# Power.net
KiCad netlist of a schematic drawn in Altium Designer
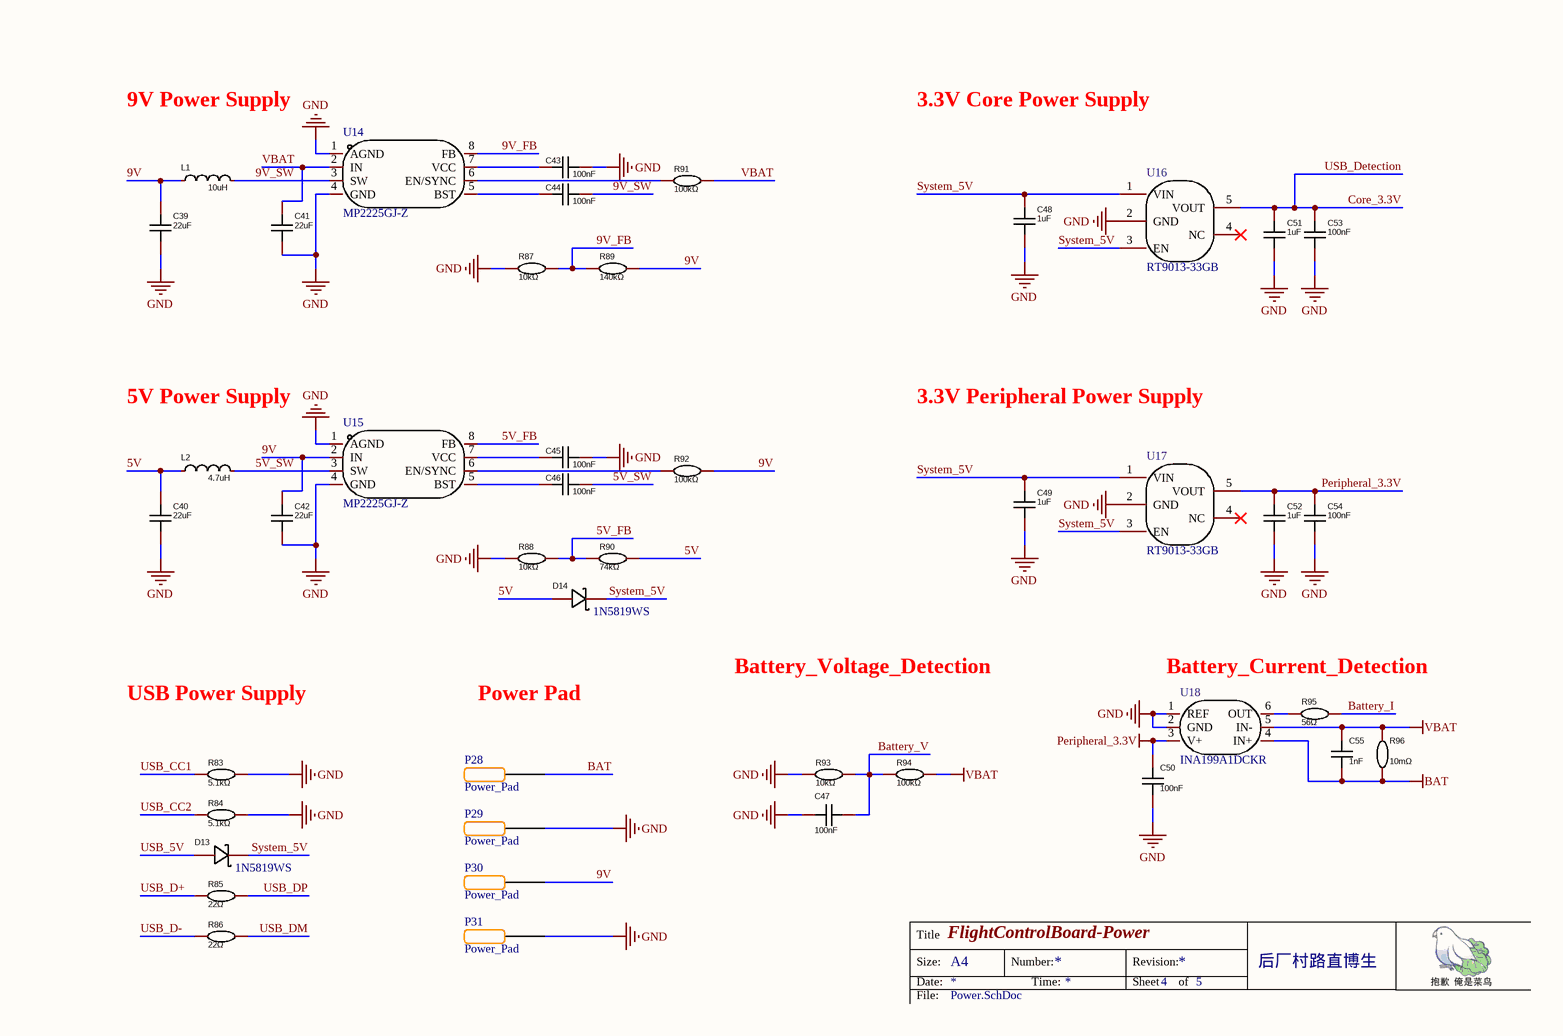
[diagram p0: Power.SchDoc]

(export (version "E")
  (design (tool "Eeschema 10.0.6"))
  (components
    (comp (ref "C39")
      (value "22uF")
      (footprint "C0603")
      (libsource (lib "Capacitor") (part "CC0603KRX7R9BB104"))
    )
    (comp (ref "C40")
      (value "22uF")
      (footprint "C0603")
      (libsource (lib "Capacitor") (part "CC0603KRX7R9BB104"))
    )
    (comp (ref "C41")
      (value "22uF")
      (footprint "C0603")
      (libsource (lib "Capacitor") (part "CC0603KRX7R9BB104"))
    )
    (comp (ref "C42")
      (value "22uF")
      (footprint "C0603")
      (libsource (lib "Capacitor") (part "CC0603KRX7R9BB104"))
    )
    (comp (ref "C43")
      (value "100nF")
      (footprint "C0201")
      (libsource (lib "Capacitor") (part "CC0603KRX7R9BB104"))
    )
    (comp (ref "C44")
      (value "100nF")
      (footprint "C0201")
      (libsource (lib "Capacitor") (part "CC0603KRX7R9BB104"))
    )
    (comp (ref "C45")
      (value "100nF")
      (footprint "C0201")
      (libsource (lib "Capacitor") (part "CC0603KRX7R9BB104"))
    )
    (comp (ref "C46")
      (value "100nF")
      (footprint "C0201")
      (libsource (lib "Capacitor") (part "CC0603KRX7R9BB104"))
    )
    (comp (ref "C47")
      (value "100nF")
      (footprint "C0201")
      (libsource (lib "Capacitor") (part "CC0603KRX7R9BB104"))
    )
    (comp (ref "C48")
      (value "1uF")
      (footprint "C0402")
      (libsource (lib "Capacitor") (part "CC0603KRX7R9BB104"))
    )
    (comp (ref "C49")
      (value "1uF")
      (footprint "C0402")
      (libsource (lib "Capacitor") (part "CC0603KRX7R9BB104"))
    )
    (comp (ref "C50")
      (value "100nF")
      (footprint "C0201")
      (libsource (lib "Capacitor") (part "CC0603KRX7R9BB104"))
    )
    (comp (ref "C51")
      (value "1uF")
      (footprint "C0402")
      (libsource (lib "Capacitor") (part "CC0603KRX7R9BB104"))
    )
    (comp (ref "C52")
      (value "1uF")
      (footprint "C0402")
      (libsource (lib "Capacitor") (part "CC0603KRX7R9BB104"))
    )
    (comp (ref "C53")
      (value "100nF")
      (footprint "C0201")
      (libsource (lib "Capacitor") (part "CC0603KRX7R9BB104"))
    )
    (comp (ref "C54")
      (value "100nF")
      (footprint "C0201")
      (libsource (lib "Capacitor") (part "CC0603KRX7R9BB104"))
    )
    (comp (ref "C55")
      (value "1nF")
      (footprint "C0201")
      (libsource (lib "Capacitor") (part "CC0603KRX7R9BB104"))
    )
    (comp (ref "D13")
      (value "1N5819WS")
      (footprint "SOD-323")
      (fields (field (name "MANUFACTURER") "Hottech(合科泰)"))
      (libsource (lib "Diode") (part "1N5819WS"))
    )
    (comp (ref "D14")
      (value "1N5819WS")
      (footprint "SOD-323")
      (fields (field (name "MANUFACTURER") "Hottech(合科泰)"))
      (libsource (lib "Diode") (part "1N5819WS"))
    )
    (comp (ref "L1")
      (value "10uH")
      (footprint "IND-SMD_L4.0-W4.0")
      (fields
        (field (name "MANUFACTURER") "cjiang(长江微电)")
        (field (name "MANUFACTURER PART") "FHD4020S-100MT")
        (field (name "TOLERANCE") "±10%")
      )
      (libsource (lib "Inductor") (part "SDFL2012T220KTF"))
    )
    (comp (ref "L2")
      (value "4.7uH")
      (footprint "IND-SMD_L4.0-W4.0")
      (fields
        (field (name "MANUFACTURER") "cjiang(长江微电)")
        (field (name "MANUFACTURER PART") "FHD4020S-4R7MT")
        (field (name "TOLERANCE") "±10%")
      )
      (libsource (lib "Inductor") (part "SDFL2012T220KTF"))
    )
    (comp (ref "P28")
      (value "Power_Pad")
      (footprint "POWER HALF HOLE")
      (libsource (lib "Pad") (part "Power_Pad"))
    )
    (comp (ref "P29")
      (value "Power_Pad")
      (footprint "POWER HALF HOLE")
      (libsource (lib "Pad") (part "Power_Pad"))
    )
    (comp (ref "P30")
      (value "Power_Pad")
      (footprint "POWER HALF HOLE")
      (libsource (lib "Pad") (part "Power_Pad"))
    )
    (comp (ref "P31")
      (value "Power_Pad")
      (footprint "POWER HALF HOLE")
      (libsource (lib "Pad") (part "Power_Pad"))
    )
    (comp (ref "R83")
      (value "5.1kΩ")
      (footprint "R0201")
      (libsource (lib "Resistor") (part "0603WAF1002T5E"))
    )
    (comp (ref "R84")
      (value "5.1kΩ")
      (footprint "R0201")
      (libsource (lib "Resistor") (part "0603WAF1002T5E"))
    )
    (comp (ref "R85") (value "22Ω") (footprint "R0201") (libsource (lib "Resistor") (part "0603WAF1002T5E")))
    (comp (ref "R86") (value "22Ω") (footprint "R0201") (libsource (lib "Resistor") (part "0603WAF1002T5E")))
    (comp (ref "R87") (value "10kΩ") (footprint "R0201") (libsource (lib "Resistor") (part "0603WAF1002T5E")))
    (comp (ref "R88") (value "10kΩ") (footprint "R0201") (libsource (lib "Resistor") (part "0603WAF1002T5E")))
    (comp (ref "R89")
      (value "140kΩ")
      (footprint "R0201")
      (libsource (lib "Resistor") (part "0603WAF1002T5E"))
    )
    (comp (ref "R90") (value "74kΩ") (footprint "R0201") (libsource (lib "Resistor") (part "0603WAF1002T5E")))
    (comp (ref "R91")
      (value "100kΩ")
      (footprint "R0201")
      (libsource (lib "Resistor") (part "0603WAF1002T5E"))
    )
    (comp (ref "R92")
      (value "100kΩ")
      (footprint "R0201")
      (libsource (lib "Resistor") (part "0603WAF1002T5E"))
    )
    (comp (ref "R93") (value "10kΩ") (footprint "R0201") (libsource (lib "Resistor") (part "0603WAF1002T5E")))
    (comp (ref "R94")
      (value "100kΩ")
      (footprint "R0201")
      (libsource (lib "Resistor") (part "0603WAF1002T5E"))
    )
    (comp (ref "R95") (value "56Ω") (footprint "R0201") (libsource (lib "Resistor") (part "0603WAF1002T5E")))
    (comp (ref "R96") (value "10mΩ") (footprint "R0805") (libsource (lib "Resistor") (part "0603WAF1002T5E")))
    (comp (ref "U14")
      (value "MP2225GJ-Z")
      (footprint "SOT-23-8")
      (libsource (lib "Power") (part "MP2225GJ-Z"))
    )
    (comp (ref "U15")
      (value "MP2225GJ-Z")
      (footprint "SOT-23-8")
      (libsource (lib "Power") (part "MP2225GJ-Z"))
    )
    (comp (ref "U16")
      (value "RT9013-33GB")
      (footprint "SOT-23-5")
      (fields (field (name "MANUFACTURER") "RICHTEK(立锜)"))
      (libsource (lib "Power") (part "RT9013-33GB"))
    )
    (comp (ref "U17")
      (value "RT9013-33GB")
      (footprint "SOT-23-5")
      (fields (field (name "MANUFACTURER") "RICHTEK(立锜)"))
      (libsource (lib "Power") (part "RT9013-33GB"))
    )
    (comp (ref "U18")
      (value "INA199A1DCKR")
      (footprint "SOT-323-6")
      (fields (field (name "MANUFACTURER") "TI(德州仪器)"))
      (libsource (lib "ESC_Drive") (part "INA199A1DCKR"))
    )
  )
  (nets
    (net (code "1") (name "/5V") (class "Default")
      (node (ref "C40") (pin "1") (pinfunction "1_1") (pintype "passive"))
      (node (ref "D14") (pin "2") (pinfunction "A_2") (pintype "passive"))
      (node (ref "L2") (pin "1") (pinfunction "1_1") (pintype "passive"))
      (node (ref "R90") (pin "2") (pinfunction "2_2") (pintype "passive"))
    )
    (net (code "2") (name "/5V_FB") (class "Default")
      (node (ref "R88") (pin "2") (pinfunction "2_2") (pintype "passive"))
      (node (ref "R90") (pin "1") (pinfunction "1_1") (pintype "passive"))
      (node (ref "U15") (pin "8") (pinfunction "FB_8") (pintype "passive"))
    )
    (net (code "3") (name "/5V_SW") (class "Default")
      (node (ref "C46") (pin "1") (pinfunction "1_1") (pintype "passive"))
      (node (ref "L2") (pin "2") (pinfunction "2_2") (pintype "passive"))
      (node (ref "U15") (pin "3") (pinfunction "SW_3") (pintype "passive"))
    )
    (net (code "4") (name "/9V") (class "Default")
      (node (ref "C39") (pin "1") (pinfunction "1_1") (pintype "passive"))
      (node (ref "C42") (pin "1") (pinfunction "1_1") (pintype "passive"))
      (node (ref "L1") (pin "1") (pinfunction "1_1") (pintype "passive"))
      (node (ref "P30") (pin "1") (pinfunction "1_1") (pintype "passive"))
      (node (ref "R89") (pin "2") (pinfunction "2_2") (pintype "passive"))
      (node (ref "R92") (pin "2") (pinfunction "2_2") (pintype "passive"))
      (node (ref "U15") (pin "2") (pinfunction "IN_2") (pintype "passive"))
    )
    (net (code "5") (name "/9V_FB") (class "Default")
      (node (ref "R87") (pin "2") (pinfunction "2_2") (pintype "passive"))
      (node (ref "R89") (pin "1") (pinfunction "1_1") (pintype "passive"))
      (node (ref "U14") (pin "8") (pinfunction "FB_8") (pintype "passive"))
    )
    (net (code "6") (name "/9V_SW") (class "Default")
      (node (ref "C44") (pin "1") (pinfunction "1_1") (pintype "passive"))
      (node (ref "L1") (pin "2") (pinfunction "2_2") (pintype "passive"))
      (node (ref "U14") (pin "3") (pinfunction "SW_3") (pintype "passive"))
    )
    (net (code "7") (name "/Battery_I") (class "Default")
      (node (ref "R95") (pin "2") (pinfunction "2_2") (pintype "passive"))
    )
    (net (code "8") (name "/Battery_V") (class "Default")
      (node (ref "C47") (pin "1") (pinfunction "1_1") (pintype "passive"))
      (node (ref "R93") (pin "2") (pinfunction "2_2") (pintype "passive"))
      (node (ref "R94") (pin "1") (pinfunction "1_1") (pintype "passive"))
    )
    (net (code "9") (name "/Core_3.3V") (class "Default")
      (node (ref "C51") (pin "1") (pinfunction "1_1") (pintype "passive"))
      (node (ref "C53") (pin "1") (pinfunction "1_1") (pintype "passive"))
      (node (ref "U16") (pin "5") (pinfunction "VOUT_5") (pintype "passive"))
    )
    (net (code "10") (name "/System_5V") (class "Default")
      (node (ref "C48") (pin "1") (pinfunction "1_1") (pintype "passive"))
      (node (ref "C49") (pin "1") (pinfunction "1_1") (pintype "passive"))
      (node (ref "D13") (pin "1") (pinfunction "K_1") (pintype "passive"))
      (node (ref "D14") (pin "1") (pinfunction "K_1") (pintype "passive"))
      (node (ref "U16") (pin "1") (pinfunction "VIN_1") (pintype "passive"))
      (node (ref "U16") (pin "3") (pinfunction "EN_3") (pintype "passive"))
      (node (ref "U17") (pin "1") (pinfunction "VIN_1") (pintype "passive"))
      (node (ref "U17") (pin "3") (pinfunction "EN_3") (pintype "passive"))
    )
    (net (code "11") (name "/USB_5V") (class "Default")
      (node (ref "D13") (pin "2") (pinfunction "A_2") (pintype "passive"))
    )
    (net (code "12") (name "/USB_CC1") (class "Default")
      (node (ref "R83") (pin "2") (pinfunction "2_2") (pintype "passive"))
    )
    (net (code "13") (name "/USB_CC2") (class "Default")
      (node (ref "R84") (pin "1") (pinfunction "1_1") (pintype "passive"))
    )
    (net (code "14") (name "/USB_D+") (class "Default")
      (node (ref "R85") (pin "1") (pinfunction "1_1") (pintype "passive"))
    )
    (net (code "15") (name "/USB_D-") (class "Default")
      (node (ref "R86") (pin "1") (pinfunction "1_1") (pintype "passive"))
    )
    (net (code "16") (name "/USB_DM") (class "Default")
      (node (ref "R86") (pin "2") (pinfunction "2_2") (pintype "passive"))
    )
    (net (code "17") (name "/USB_DP") (class "Default")
      (node (ref "R85") (pin "2") (pinfunction "2_2") (pintype "passive"))
    )
    (net (code "18") (name "BAT") (class "Default")
      (node (ref "C55") (pin "2") (pinfunction "2_2") (pintype "passive"))
      (node (ref "P28") (pin "1") (pinfunction "1_1") (pintype "passive"))
      (node (ref "R96") (pin "1") (pinfunction "1_1") (pintype "passive"))
      (node (ref "U18") (pin "4") (pinfunction "IN+_4") (pintype "passive"))
    )
    (net (code "19") (name "GND") (class "Default")
      (node (ref "C39") (pin "2") (pinfunction "2_2") (pintype "passive"))
      (node (ref "C40") (pin "2") (pinfunction "2_2") (pintype "passive"))
      (node (ref "C41") (pin "2") (pinfunction "2_2") (pintype "passive"))
      (node (ref "C42") (pin "2") (pinfunction "2_2") (pintype "passive"))
      (node (ref "C43") (pin "1") (pinfunction "1_1") (pintype "passive"))
      (node (ref "C45") (pin "1") (pinfunction "1_1") (pintype "passive"))
      (node (ref "C47") (pin "2") (pinfunction "2_2") (pintype "passive"))
      (node (ref "C48") (pin "2") (pinfunction "2_2") (pintype "passive"))
      (node (ref "C49") (pin "2") (pinfunction "2_2") (pintype "passive"))
      (node (ref "C50") (pin "2") (pinfunction "2_2") (pintype "passive"))
      (node (ref "C51") (pin "2") (pinfunction "2_2") (pintype "passive"))
      (node (ref "C52") (pin "2") (pinfunction "2_2") (pintype "passive"))
      (node (ref "C53") (pin "2") (pinfunction "2_2") (pintype "passive"))
      (node (ref "C54") (pin "2") (pinfunction "2_2") (pintype "passive"))
      (node (ref "P29") (pin "1") (pinfunction "1_1") (pintype "passive"))
      (node (ref "P31") (pin "1") (pinfunction "1_1") (pintype "passive"))
      (node (ref "R83") (pin "1") (pinfunction "1_1") (pintype "passive"))
      (node (ref "R84") (pin "2") (pinfunction "2_2") (pintype "passive"))
      (node (ref "R87") (pin "1") (pinfunction "1_1") (pintype "passive"))
      (node (ref "R88") (pin "1") (pinfunction "1_1") (pintype "passive"))
      (node (ref "R93") (pin "1") (pinfunction "1_1") (pintype "passive"))
      (node (ref "U14") (pin "1") (pinfunction "AGND_1") (pintype "passive"))
      (node (ref "U14") (pin "4") (pinfunction "GND_4") (pintype "passive"))
      (node (ref "U15") (pin "1") (pinfunction "AGND_1") (pintype "passive"))
      (node (ref "U15") (pin "4") (pinfunction "GND_4") (pintype "passive"))
      (node (ref "U16") (pin "2") (pinfunction "GND_2") (pintype "passive"))
      (node (ref "U17") (pin "2") (pinfunction "GND_2") (pintype "passive"))
      (node (ref "U18") (pin "1") (pinfunction "REF_1") (pintype "passive"))
      (node (ref "U18") (pin "2") (pinfunction "GND_2") (pintype "passive"))
    )
    (net (code "20") (name "Net-(U14-BST)") (class "Default")
      (node (ref "C44") (pin "2") (pinfunction "2_2") (pintype "passive"))
      (node (ref "U14") (pin "5") (pinfunction "BST_5") (pintype "passive"))
    )
    (net (code "21") (name "Net-(U14-EN{slash}SYNC)") (class "Default")
      (node (ref "R91") (pin "1") (pinfunction "1_1") (pintype "passive"))
      (node (ref "U14") (pin "6") (pinfunction "EN/SYNC_6") (pintype "passive"))
    )
    (net (code "22") (name "Net-(U14-VCC)") (class "Default")
      (node (ref "C43") (pin "2") (pinfunction "2_2") (pintype "passive"))
      (node (ref "U14") (pin "7") (pinfunction "VCC_7") (pintype "passive"))
    )
    (net (code "23") (name "Net-(U15-BST)") (class "Default")
      (node (ref "C46") (pin "2") (pinfunction "2_2") (pintype "passive"))
      (node (ref "U15") (pin "5") (pinfunction "BST_5") (pintype "passive"))
    )
    (net (code "24") (name "Net-(U15-EN{slash}SYNC)") (class "Default")
      (node (ref "R92") (pin "1") (pinfunction "1_1") (pintype "passive"))
      (node (ref "U15") (pin "6") (pinfunction "EN/SYNC_6") (pintype "passive"))
    )
    (net (code "25") (name "Net-(U15-VCC)") (class "Default")
      (node (ref "C45") (pin "2") (pinfunction "2_2") (pintype "passive"))
      (node (ref "U15") (pin "7") (pinfunction "VCC_7") (pintype "passive"))
    )
    (net (code "26") (name "Net-(U18-OUT)") (class "Default")
      (node (ref "R95") (pin "1") (pinfunction "1_1") (pintype "passive"))
      (node (ref "U18") (pin "6") (pinfunction "OUT_6") (pintype "passive"))
    )
    (net (code "27") (name "Peripheral_3.3V") (class "Default")
      (node (ref "C50") (pin "1") (pinfunction "1_1") (pintype "passive"))
      (node (ref "C52") (pin "1") (pinfunction "1_1") (pintype "passive"))
      (node (ref "C54") (pin "1") (pinfunction "1_1") (pintype "passive"))
      (node (ref "U17") (pin "5") (pinfunction "VOUT_5") (pintype "passive"))
      (node (ref "U18") (pin "3") (pinfunction "V+_3") (pintype "passive"))
    )
    (net (code "28") (name "VBAT") (class "Default")
      (node (ref "C41") (pin "1") (pinfunction "1_1") (pintype "passive"))
      (node (ref "C55") (pin "1") (pinfunction "1_1") (pintype "passive"))
      (node (ref "R91") (pin "2") (pinfunction "2_2") (pintype "passive"))
      (node (ref "R94") (pin "2") (pinfunction "2_2") (pintype "passive"))
      (node (ref "R96") (pin "2") (pinfunction "2_2") (pintype "passive"))
      (node (ref "U14") (pin "2") (pinfunction "IN_2") (pintype "passive"))
      (node (ref "U18") (pin "5") (pinfunction "IN-_5") (pintype "passive"))
    )
    (net (code "29") (name "unconnected-(U16-NC-Pad4)") (class "Default")
      (node (ref "U16") (pin "4") (pinfunction "NC_4") (pintype "passive+no_connect"))
    )
    (net (code "30") (name "unconnected-(U17-NC-Pad4)") (class "Default")
      (node (ref "U17") (pin "4") (pinfunction "NC_4") (pintype "passive+no_connect"))
    )
  )
)
